# BMS-S05-V00-Isolation.net
KiCad netlist of a schematic drawn in Altium Designer
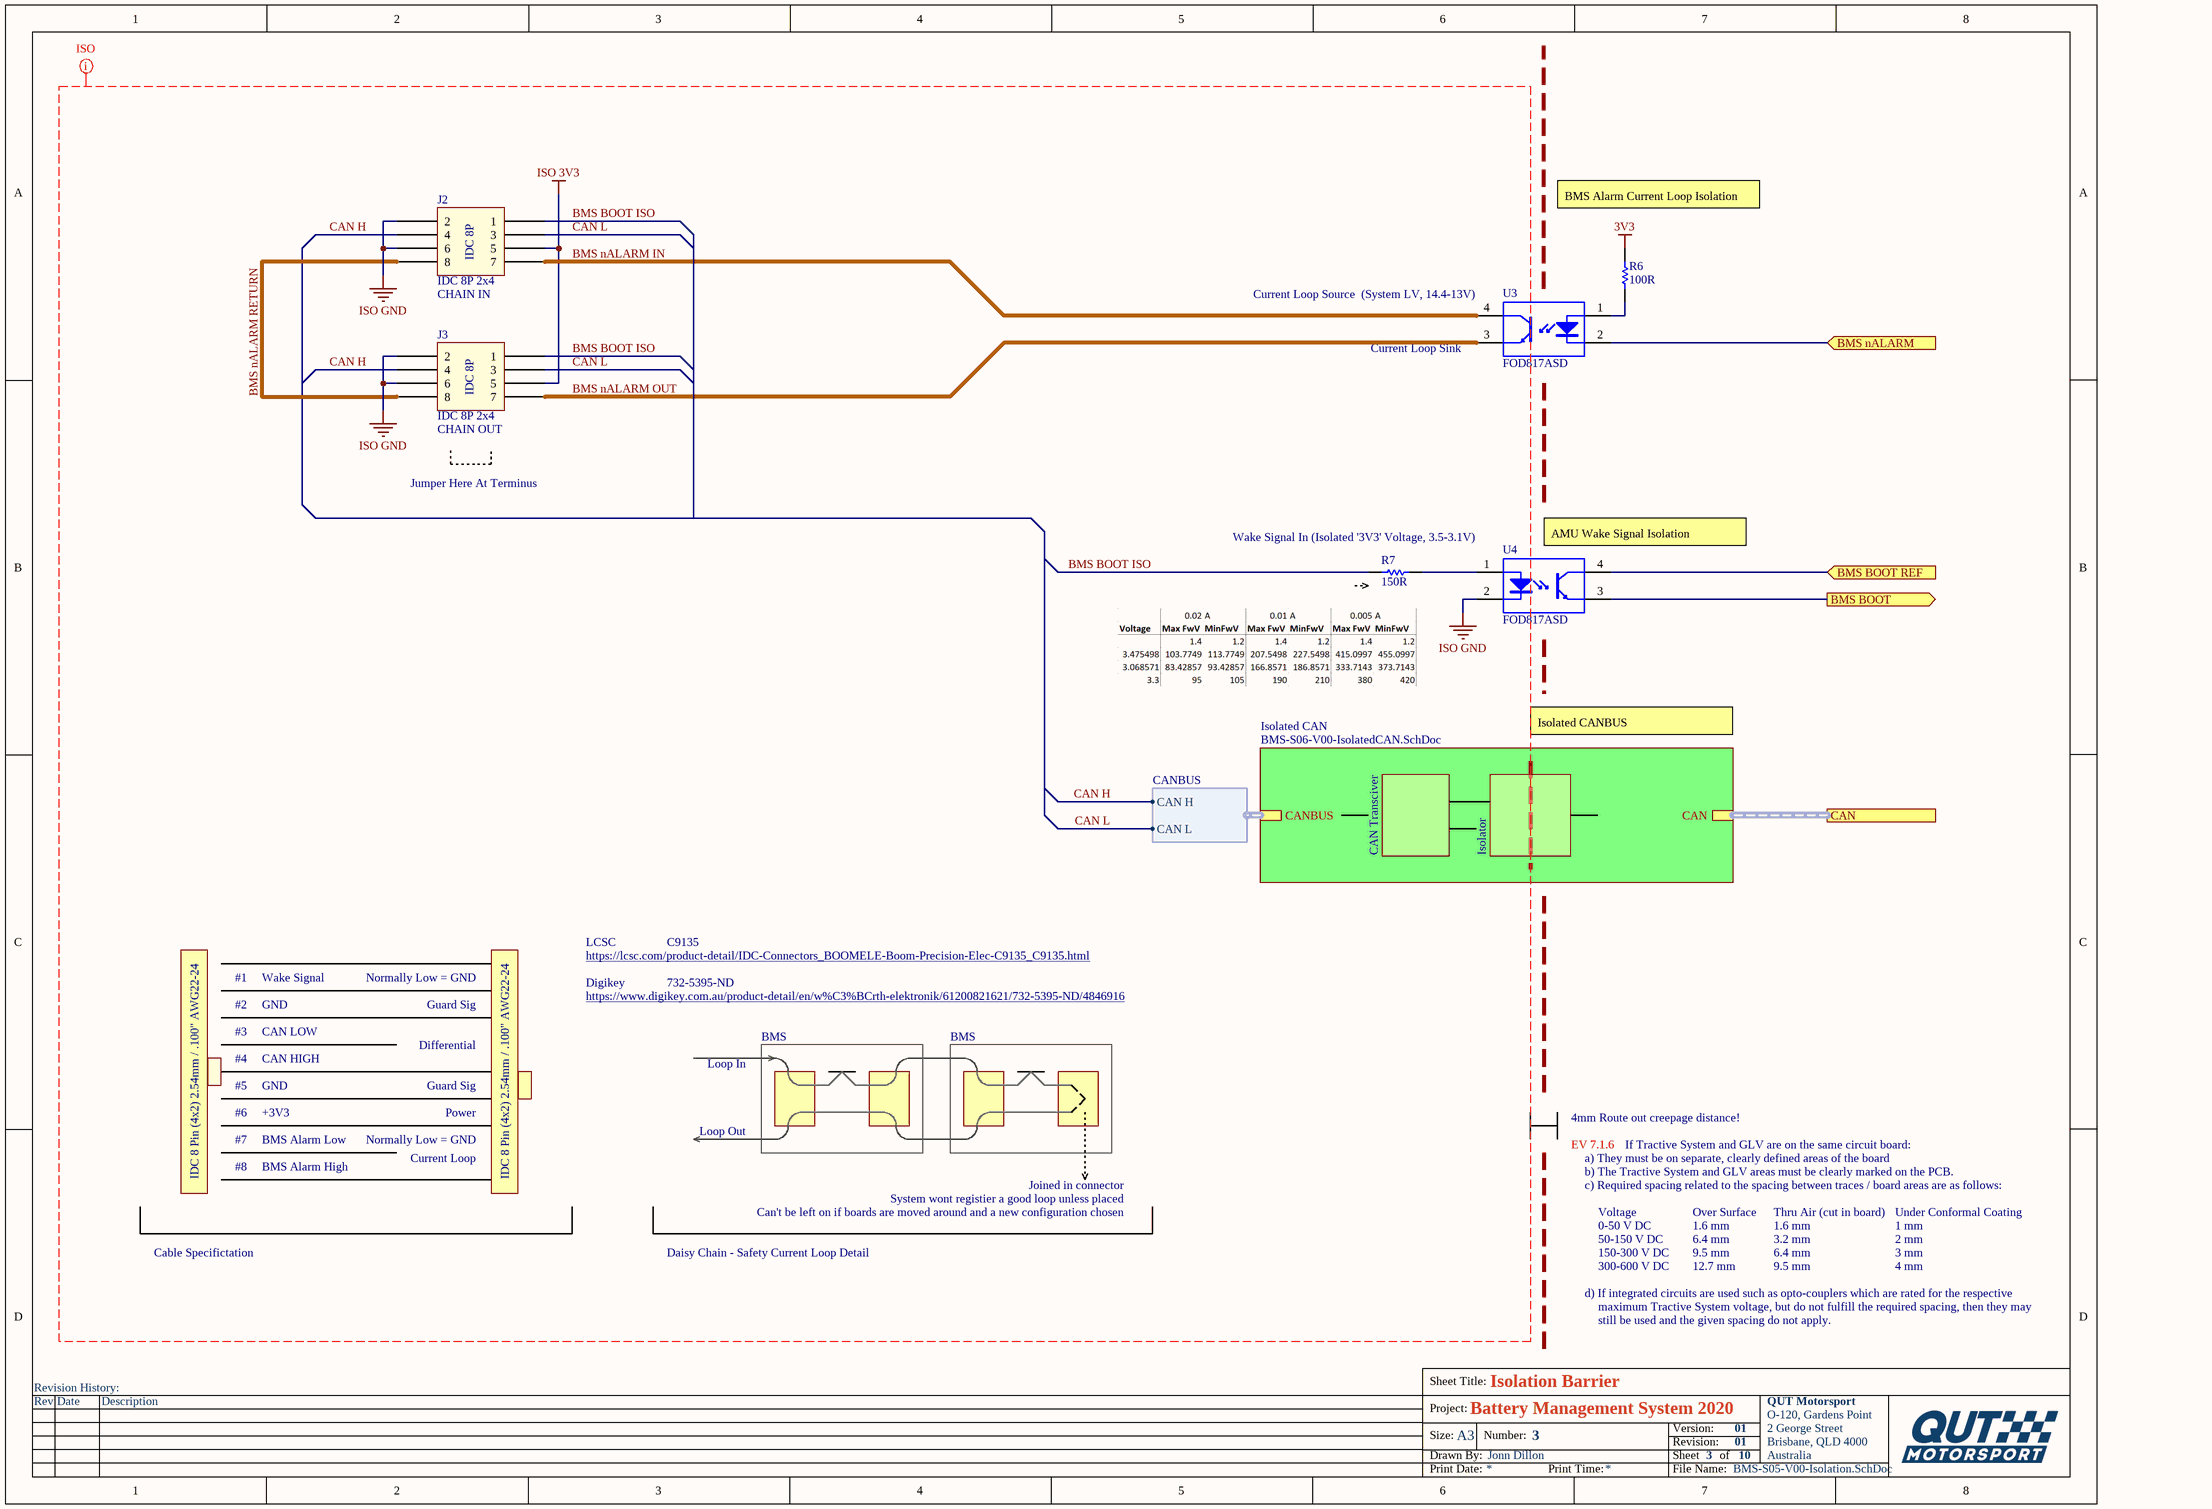
[diagram p0: BMS-S05-V00-Isolation.SchDoc]

(export (version "E")
  (design (tool "Eeschema 10.0.6"))
  (components
    (comp (ref "J2")
      (value "IDC 8P 2x4")
      (footprint "IDC 2.54MM 8P")
      (description "IDC 8P 2x5")
      (libsource (lib "IDCConnectors") (part "IDC 8P 2x4"))
    )
    (comp (ref "J3")
      (value "IDC 8P 2x4")
      (footprint "IDC 2.54MM 8P")
      (description "IDC 8P 2x5")
      (libsource (lib "IDCConnectors") (part "IDC 8P 2x4"))
    )
    (comp (ref "R6")
      (value "100R")
      (footprint "Res_ThinFilm_0603")
      (description "Resistor, SMD, 100R, 0.1W, 5%, 0603")
      (libsource (lib "StandardResistors") (part "100R 5%, 0603"))
    )
    (comp (ref "R7")
      (value "150R")
      (footprint "Res_ThinFilm_0603")
      (description "Resistor, SMD, 150R, 0.1W, 5%, 0603")
      (libsource (lib "StandardResistors") (part "150R 5% 0603"))
    )
    (comp (ref "U3")
      (value "FOD817ASD")
      (footprint "FOD817ASD")
      (description "Optoisolator 5kV Transistor 4SMD")
      (libsource (lib "QUTMS_OctocouplerLibrary") (part "FOD817ASD"))
    )
    (comp (ref "U4")
      (value "FOD817ASD")
      (footprint "FOD817ASD")
      (description "Optoisolator 5kV Transistor 4SMD")
      (libsource (lib "QUTMS_OctocouplerLibrary") (part "FOD817ASD"))
    )
  )
  (nets
    (net (code "3") (name "/BMS BOOT") (class "Default")
      (node (ref "U4") (pin "3") (pinfunction "EMITTER_3") (pintype "passive"))
    )
    (net (code "4") (name "/BMS BOOT ISO") (class "Default")
      (node (ref "J2") (pin "1") (pinfunction "1_1") (pintype "passive"))
      (node (ref "J3") (pin "1") (pinfunction "1_1") (pintype "passive"))
      (node (ref "R7") (pin "1") (pinfunction "1_1") (pintype "passive"))
    )
    (net (code "5") (name "/BMS BOOT REF") (class "Default")
      (node (ref "U4") (pin "4") (pinfunction "COLLECTOR_4") (pintype "passive"))
    )
    (net (code "6") (name "/BMS nALARM") (class "Default")
      (node (ref "U3") (pin "2") (pinfunction "CATHODE_2") (pintype "passive"))
    )
    (net (code "7") (name "/BMS nALARM IN") (class "Default")
      (node (ref "J2") (pin "7") (pinfunction "7_7") (pintype "passive"))
      (node (ref "U3") (pin "4") (pinfunction "COLLECTOR_4") (pintype "passive"))
    )
    (net (code "8") (name "/BMS nALARM OUT") (class "Default")
      (node (ref "J3") (pin "7") (pinfunction "7_7") (pintype "passive"))
      (node (ref "U3") (pin "3") (pinfunction "EMITTER_3") (pintype "passive"))
    )
    (net (code "9") (name "/BMS nALARM RETURN") (class "Default")
      (node (ref "J2") (pin "8") (pinfunction "8_8") (pintype "passive"))
      (node (ref "J3") (pin "8") (pinfunction "8_8") (pintype "passive"))
    )
    (net (code "10") (name "/CAN H") (class "Default")
      (node (ref "J2") (pin "4") (pinfunction "4_4") (pintype "passive"))
      (node (ref "J3") (pin "4") (pinfunction "4_4") (pintype "passive"))
    )
    (net (code "11") (name "/CAN L") (class "Default")
      (node (ref "J2") (pin "3") (pinfunction "3_3") (pintype "passive"))
      (node (ref "J3") (pin "3") (pinfunction "3_3") (pintype "passive"))
    )
    (net (code "14") (name "3V3") (class "Default")
      (node (ref "R6") (pin "2") (pinfunction "2_2") (pintype "passive"))
    )
    (net (code "15") (name "ISO 3V3") (class "Default")
      (node (ref "J2") (pin "5") (pinfunction "5_5") (pintype "passive"))
      (node (ref "J3") (pin "5") (pinfunction "5_5") (pintype "passive"))
    )
    (net (code "16") (name "ISO GND") (class "Default")
      (node (ref "J2") (pin "2") (pinfunction "2_2") (pintype "passive"))
      (node (ref "J2") (pin "6") (pinfunction "6_6") (pintype "passive"))
      (node (ref "J3") (pin "2") (pinfunction "2_2") (pintype "passive"))
      (node (ref "J3") (pin "6") (pinfunction "6_6") (pintype "passive"))
      (node (ref "U4") (pin "2") (pinfunction "CATHODE_2") (pintype "passive"))
    )
    (net (code "17") (name "Net-(U3-ANODE)") (class "Default")
      (node (ref "R6") (pin "1") (pinfunction "1_1") (pintype "passive"))
      (node (ref "U3") (pin "1") (pinfunction "ANODE_1") (pintype "passive"))
    )
    (net (code "18") (name "Net-(U4-ANODE)") (class "Default")
      (node (ref "R7") (pin "2") (pinfunction "2_2") (pintype "passive"))
      (node (ref "U4") (pin "1") (pinfunction "ANODE_1") (pintype "passive"))
    )
  )
)
